# 12_-CAMERA_POWER.net
KiCad netlist of a schematic drawn in Altium Designer
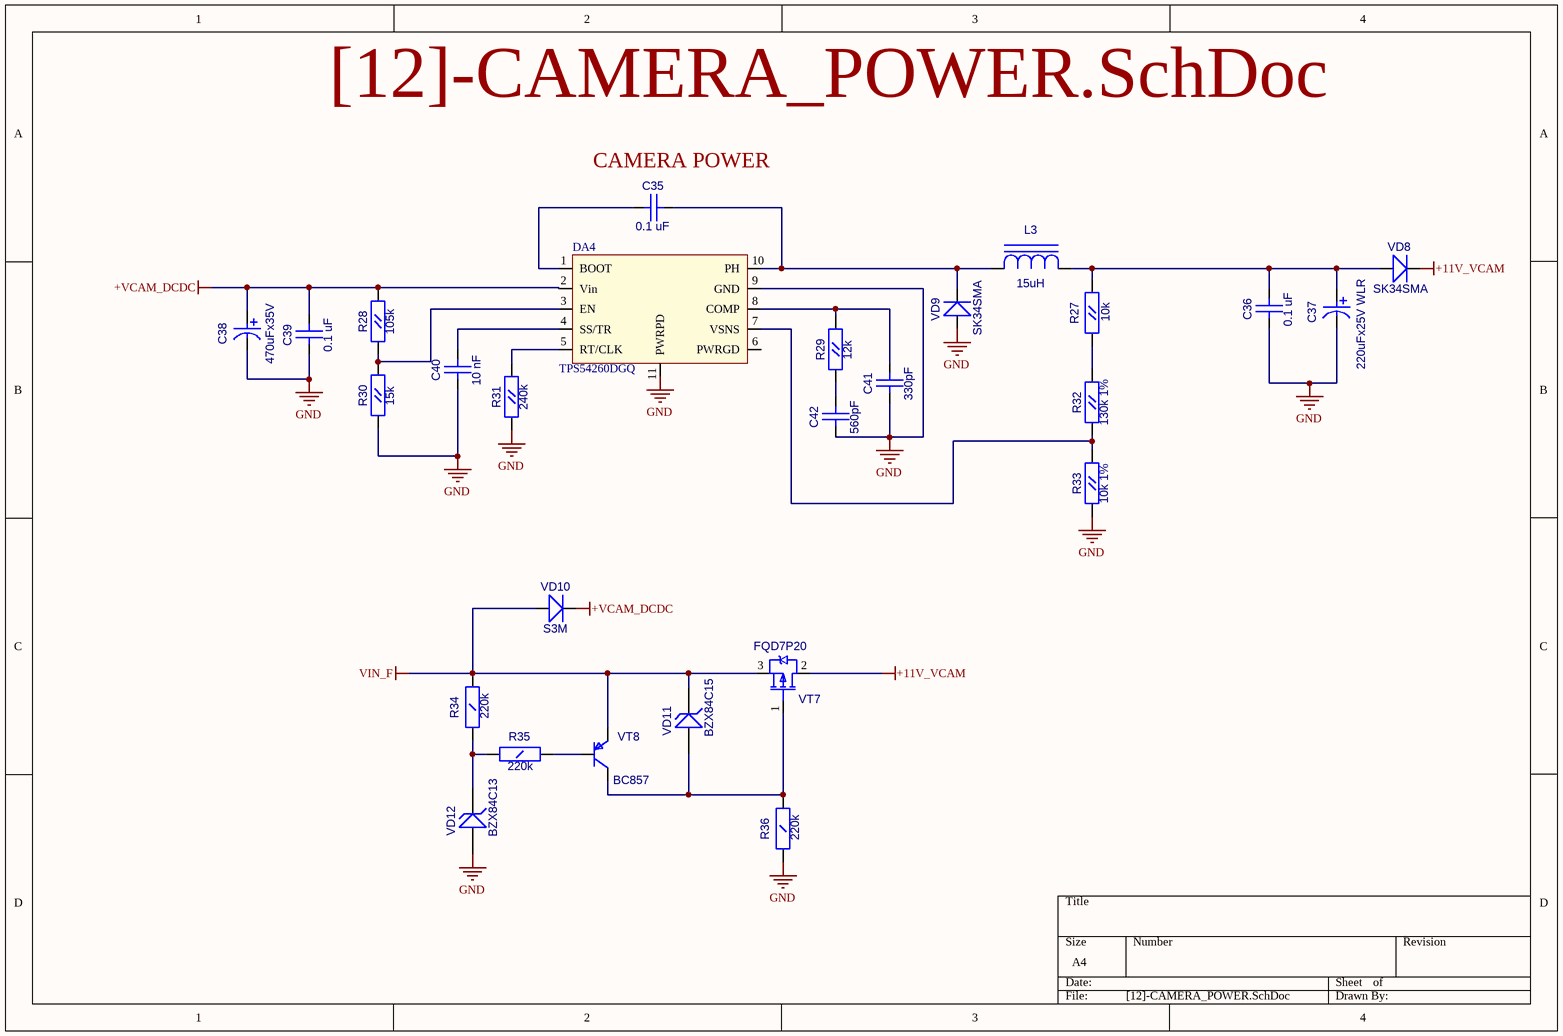
[diagram p0: [12]-CAMERA_POWER.SchDoc]

(export (version "E")
  (design (tool "Eeschema 10.0.6"))
  (components
    (comp (ref "C35")
      (value "0.1 uF")
      (footprint "CC0603")
      (description "CC0603")
      (libsource (lib "gprs_modem_2") (part "CC0603"))
    )
    (comp (ref "C36")
      (value "0.1 uF")
      (footprint "CC0603")
      (description "CC0603")
      (libsource (lib "gprs_modem_2") (part "CC0603"))
    )
    (comp (ref "C37")
      (value "220uFx25V WLR")
      (footprint "CC8X3.5")
      (description "CAP0.35")
      (libsource (lib "gprs_modem_2") (part "CAP0.35"))
    )
    (comp (ref "C38")
      (value "470uFx35V")
      (footprint "CC16X10_CAP0.5(1)(Primary)")
      (description "CAP0.5(1)")
      (libsource (lib "gprs_modem_2") (part "CAP0.5(1)"))
    )
    (comp (ref "C39")
      (value "0.1 uF")
      (footprint "CC0603")
      (description "CC0603")
      (libsource (lib "gprs_modem_2") (part "CC0603"))
    )
    (comp (ref "C40")
      (value "10 nF")
      (footprint "CC0603")
      (description "CC0603")
      (libsource (lib "gprs_modem_2") (part "CC0603"))
    )
    (comp (ref "C41")
      (value "330pF")
      (footprint "CC0603")
      (description "CC0603")
      (libsource (lib "gprs_modem_2") (part "CC0603"))
    )
    (comp (ref "C42")
      (value "560pF")
      (footprint "CC0603")
      (description "CC0603")
      (libsource (lib "gprs_modem_2") (part "CC0603"))
    )
    (comp (ref "DA4")
      (value "TPS54260DGQ")
      (footprint "S-PDSO-G10")
      (libsource (lib "gprs_modem_2") (part "TPS54260DGQ"))
    )
    (comp (ref "L3")
      (value "15uH")
      (footprint "SDR0805")
      (description "SDR0805")
      (libsource (lib "gprs_modem_2") (part "SDR0805"))
    )
    (comp (ref "R27")
      (value "10k")
      (footprint "RC0603")
      (description "RC0603")
      (libsource (lib "fizik_lib") (part "RC0603"))
    )
    (comp (ref "R28")
      (value "105k")
      (footprint "RC0603")
      (description "RC0603")
      (libsource (lib "gprs_modem_2") (part "RC0603"))
    )
    (comp (ref "R29")
      (value "12k")
      (footprint "RC0603")
      (description "RC0603")
      (libsource (lib "gprs_modem_2") (part "RC0603"))
    )
    (comp (ref "R30")
      (value "15k")
      (footprint "RC0603")
      (description "RC0603")
      (libsource (lib "gprs_modem_2") (part "RC0603"))
    )
    (comp (ref "R31")
      (value "240k")
      (footprint "RC0603")
      (description "RC0603")
      (libsource (lib "gprs_modem_2") (part "RC0603"))
    )
    (comp (ref "R32")
      (value "130k 1%")
      (footprint "RC0603")
      (description "RC0603")
      (libsource (lib "gprs_modem_2") (part "RC0603"))
    )
    (comp (ref "R33")
      (value "10k 1%")
      (footprint "RC0603")
      (description "RC0603")
      (libsource (lib "gprs_modem_2") (part "RC0603"))
    )
    (comp (ref "R34")
      (value "220k")
      (footprint "RC1206")
      (description "RC1206")
      (libsource (lib "fizik_lib") (part "RC1206"))
    )
    (comp (ref "R35")
      (value "220k")
      (footprint "RC1206")
      (description "RC1206")
      (libsource (lib "fizik_lib") (part "RC1206"))
    )
    (comp (ref "R36")
      (value "220k")
      (footprint "RC1206")
      (description "RC1206")
      (libsource (lib "fizik_lib") (part "RC1206"))
    )
    (comp (ref "VD8")
      (value "SK34SMA")
      (footprint "SMA")
      (description "Schottky Rectifier")
      (libsource (lib "gprs_modem") (part "SK34SMA"))
    )
    (comp (ref "VD9")
      (value "SK34SMA")
      (footprint "SMA")
      (description "Schottky Rectifier")
      (libsource (lib "gprs_modem") (part "SK34SMA"))
    )
    (comp (ref "VD10")
      (value "S3M")
      (footprint "SMC")
      (description "Schottky Rectifier")
      (libsource (lib "fizik_lib") (part "S3A"))
    )
    (comp (ref "VD11")
      (value "BZX84C15")
      (footprint "SOT-23(123)")
      (description "Zener Voltage Regulator Diode")
      (libsource (lib "fizik_lib") (part "BZX84"))
    )
    (comp (ref "VD12")
      (value "BZX84C13")
      (footprint "SOT-23(123)")
      (description "Zener Voltage Regulator Diode")
      (libsource (lib "fizik_lib") (part "BZX84"))
    )
    (comp (ref "VT7")
      (value "FQD7P20")
      (footprint "D-PAK(TO-252AA)")
      (description "HEXFET Power MOSFET")
      (libsource (lib "gprs_modem_2") (part "IRFR9220"))
    )
    (comp (ref "VT8")
      (value "BC857")
      (footprint "SOT-23(123)")
      (description "PNP 100ma transistor")
      (libsource (lib "gprs_modem_2") (part "BC857B"))
    )
  )
  (nets
    (net (code "1") (name "+11V_VCAM") (class "Default")
      (node (ref "VD8") (pin "2") (pinfunction "K_2") (pintype "passive"))
      (node (ref "VT7") (pin "2") (pinfunction "D_2") (pintype "passive"))
    )
    (net (code "2") (name "+VCAM_DCDC") (class "Default")
      (node (ref "C38") (pin "2") (pintype "passive"))
      (node (ref "C39") (pin "1") (pinfunction "A_1") (pintype "passive"))
      (node (ref "DA4") (pin "2") (pinfunction "Vin_2") (pintype "passive"))
      (node (ref "R28") (pin "2") (pinfunction "B_2") (pintype "passive"))
      (node (ref "VD10") (pin "2") (pinfunction "K_2") (pintype "passive"))
    )
    (net (code "3") (name "GND") (class "Default")
      (node (ref "C36") (pin "2") (pinfunction "B_2") (pintype "passive"))
      (node (ref "C37") (pin "2") (pintype "passive"))
      (node (ref "C38") (pin "1") (pintype "passive"))
      (node (ref "C39") (pin "2") (pinfunction "B_2") (pintype "passive"))
      (node (ref "C40") (pin "2") (pinfunction "B_2") (pintype "passive"))
      (node (ref "C41") (pin "2") (pinfunction "B_2") (pintype "passive"))
      (node (ref "C42") (pin "2") (pinfunction "B_2") (pintype "passive"))
      (node (ref "DA4") (pin "11") (pinfunction "PWRPD_11") (pintype "passive"))
      (node (ref "DA4") (pin "9") (pinfunction "GND_9") (pintype "passive"))
      (node (ref "R30") (pin "1") (pinfunction "A_1") (pintype "passive"))
      (node (ref "R31") (pin "1") (pinfunction "A_1") (pintype "passive"))
      (node (ref "R33") (pin "1") (pinfunction "A_1") (pintype "passive"))
      (node (ref "R36") (pin "1") (pinfunction "A_1") (pintype "passive"))
      (node (ref "VD12") (pin "1") (pinfunction "A_1") (pintype "passive"))
      (node (ref "VD9") (pin "1") (pinfunction "A_1") (pintype "passive"))
    )
    (net (code "4") (name "Net-(C35-A)") (class "Default")
      (node (ref "C35") (pin "1") (pinfunction "A_1") (pintype "passive"))
      (node (ref "DA4") (pin "10") (pinfunction "PH_10") (pintype "passive"))
      (node (ref "L3") (pin "1") (pinfunction "C_1") (pintype "passive"))
      (node (ref "VD9") (pin "2") (pinfunction "K_2") (pintype "passive"))
    )
    (net (code "5") (name "Net-(C35-B)") (class "Default")
      (node (ref "C35") (pin "2") (pinfunction "B_2") (pintype "passive"))
      (node (ref "DA4") (pin "1") (pinfunction "BOOT_1") (pintype "passive"))
    )
    (net (code "6") (name "Net-(C36-A)") (class "Default")
      (node (ref "C36") (pin "1") (pinfunction "A_1") (pintype "passive"))
      (node (ref "C37") (pin "1") (pintype "passive"))
      (node (ref "L3") (pin "2") (pinfunction "A_2") (pintype "passive"))
      (node (ref "R27") (pin "2") (pinfunction "B_2") (pintype "passive"))
      (node (ref "VD8") (pin "1") (pinfunction "A_1") (pintype "passive"))
    )
    (net (code "7") (name "Net-(C40-A)") (class "Default")
      (node (ref "C40") (pin "1") (pinfunction "A_1") (pintype "passive"))
      (node (ref "DA4") (pin "4") (pinfunction "SS/TR_4") (pintype "passive"))
    )
    (net (code "8") (name "Net-(C41-A)") (class "Default")
      (node (ref "C41") (pin "1") (pinfunction "A_1") (pintype "passive"))
      (node (ref "DA4") (pin "8") (pinfunction "COMP_8") (pintype "passive"))
      (node (ref "R29") (pin "2") (pinfunction "B_2") (pintype "passive"))
    )
    (net (code "9") (name "Net-(C42-A)") (class "Default")
      (node (ref "C42") (pin "1") (pinfunction "A_1") (pintype "passive"))
      (node (ref "R29") (pin "1") (pinfunction "A_1") (pintype "passive"))
    )
    (net (code "10") (name "Net-(DA4-EN)") (class "Default")
      (node (ref "DA4") (pin "3") (pinfunction "EN_3") (pintype "passive"))
      (node (ref "R28") (pin "1") (pinfunction "A_1") (pintype "passive"))
      (node (ref "R30") (pin "2") (pinfunction "B_2") (pintype "passive"))
    )
    (net (code "11") (name "Net-(DA4-RT{slash}CLK)") (class "Default")
      (node (ref "DA4") (pin "5") (pinfunction "RT/CLK_5") (pintype "passive"))
      (node (ref "R31") (pin "2") (pinfunction "B_2") (pintype "passive"))
    )
    (net (code "12") (name "Net-(DA4-VSNS)") (class "Default")
      (node (ref "DA4") (pin "7") (pinfunction "VSNS_7") (pintype "passive"))
      (node (ref "R32") (pin "1") (pinfunction "A_1") (pintype "passive"))
      (node (ref "R33") (pin "2") (pinfunction "B_2") (pintype "passive"))
    )
    (net (code "13") (name "Net-(R27-A)") (class "Default")
      (node (ref "R27") (pin "1") (pinfunction "A_1") (pintype "passive"))
      (node (ref "R32") (pin "2") (pinfunction "B_2") (pintype "passive"))
    )
    (net (code "14") (name "Net-(R34-A)") (class "Default")
      (node (ref "R34") (pin "1") (pinfunction "A_1") (pintype "passive"))
      (node (ref "R35") (pin "1") (pinfunction "A_1") (pintype "passive"))
      (node (ref "VD12") (pin "3") (pinfunction "K_3") (pintype "passive"))
    )
    (net (code "15") (name "Net-(R35-B)") (class "Default")
      (node (ref "R35") (pin "2") (pinfunction "B_2") (pintype "passive"))
      (node (ref "VT8") (pin "1") (pinfunction "B_1") (pintype "passive"))
    )
    (net (code "16") (name "Net-(R36-B)") (class "Default")
      (node (ref "R36") (pin "2") (pinfunction "B_2") (pintype "passive"))
      (node (ref "VD11") (pin "1") (pinfunction "A_1") (pintype "passive"))
      (node (ref "VT7") (pin "1") (pinfunction "G_1") (pintype "passive"))
      (node (ref "VT8") (pin "3") (pinfunction "C_3") (pintype "passive"))
    )
    (net (code "17") (name "VIN_F") (class "Default")
      (node (ref "R34") (pin "2") (pinfunction "B_2") (pintype "passive"))
      (node (ref "VD10") (pin "1") (pinfunction "A_1") (pintype "passive"))
      (node (ref "VD11") (pin "3") (pinfunction "K_3") (pintype "passive"))
      (node (ref "VT7") (pin "3") (pinfunction "S_3") (pintype "passive"))
      (node (ref "VT8") (pin "2") (pinfunction "E_2") (pintype "passive"))
    )
    (net (code "18") (name "unconnected-(DA4-PWRGD-Pad6)") (class "Default")
      (node (ref "DA4") (pin "6") (pinfunction "PWRGD_6") (pintype "passive"))
    )
  )
)
